# untitled.net
KiCad netlist of a schematic drawn in EAGLE
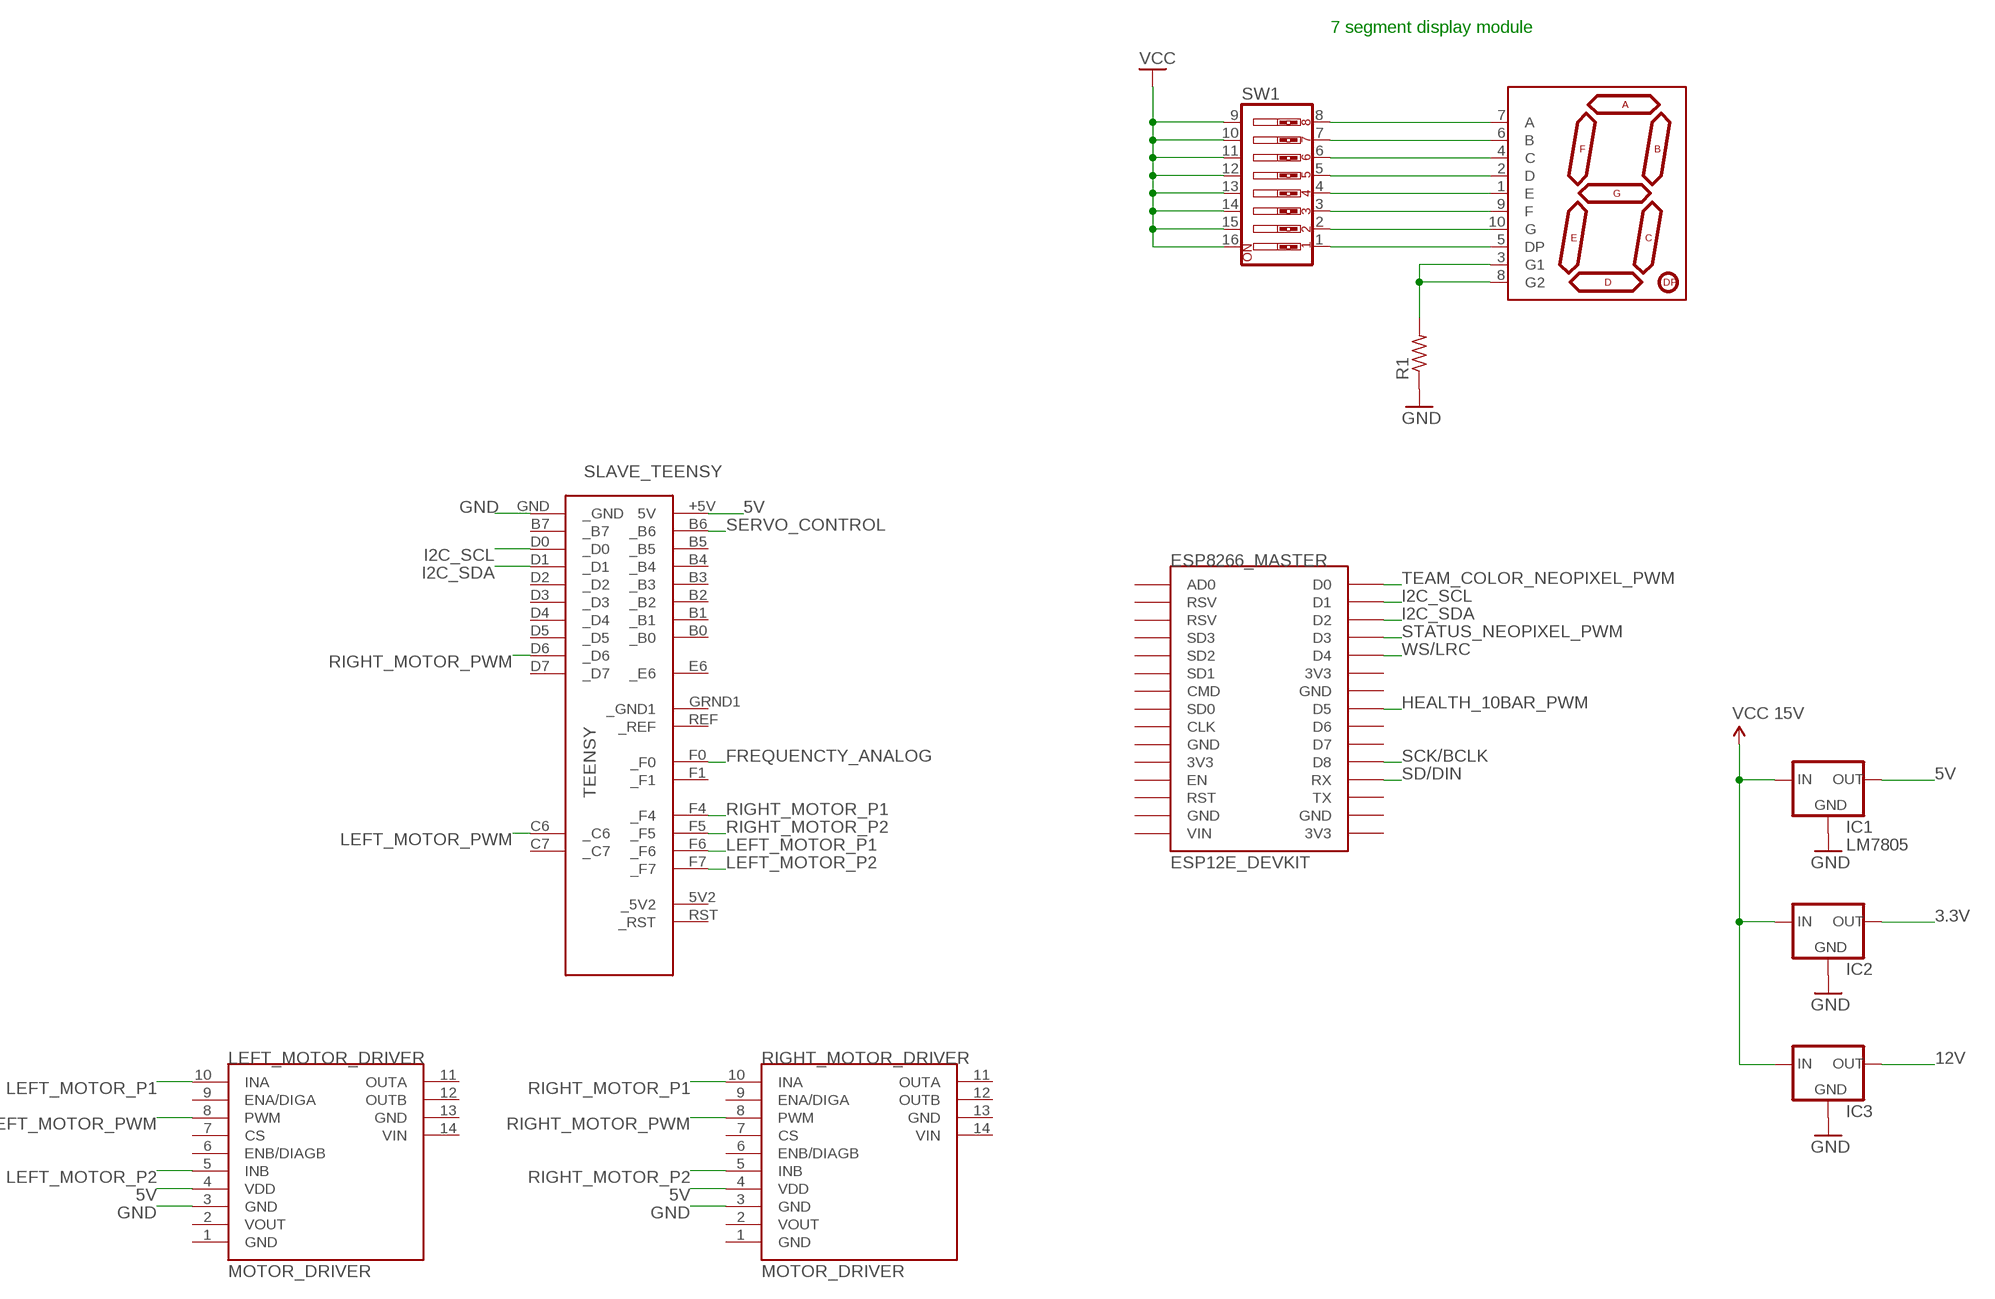
[diagram p0: schematic, sheet 1]

(export (version "E")
  (design (tool "Eeschema 10.0.6"))
  (components
    (comp (ref "ESP8266_MASTER")
      (value "ESP12E_DEVKIT")
      (footprint "eagle-import:ESP12E_DEVKIT")
      (libsource (lib "eagle-import") (part "ESP12E_DEVKIT"))
    )
    (comp (ref "IC1")
      (value "LM7805")
      (footprint "eagle-import:TO-220-ALT")
      (libsource (lib "eagle-import") (part "V_REG_78XX-TO-220"))
    )
    (comp (ref "IC2")
      (value "V_REG_78XX-TO-220")
      (footprint "eagle-import:TO-220-ALT")
      (libsource (lib "eagle-import") (part "V_REG_78XX-TO-220"))
    )
    (comp (ref "IC3")
      (value "V_REG_78XX-TO-220")
      (footprint "eagle-import:TO-220-ALT")
      (libsource (lib "eagle-import") (part "V_REG_78XX-TO-220"))
    )
    (comp (ref "LEFT_MOTOR_DRIVER")
      (value "MOTOR_DRIVER")
      (footprint "eagle-import:VNH5019A_MOTORDRIVER_CARIER_POLOLU")
      (libsource (lib "eagle-import") (part "MOTOR_DRIVER"))
    )
    (comp (ref "R1")
      (value "R-US_0204/2V")
      (footprint "eagle-import:0204V")
      (libsource (lib "eagle-import") (part "R-US_0204/2V"))
    )
    (comp (ref "RIGHT_MOTOR_DRIVER")
      (value "MOTOR_DRIVER")
      (footprint "eagle-import:VNH5019A_MOTORDRIVER_CARIER_POLOLU")
      (libsource (lib "eagle-import") (part "MOTOR_DRIVER"))
    )
    (comp (ref "SLAVE_TEENSY")
      (value "TEENSY")
      (footprint "eagle-import:TEENSY")
      (libsource (lib "eagle-import") (part "TEENSY"))
    )
    (comp (ref "SW1")
      (value "SW_DIP-8")
      (footprint "eagle-import:DIPSWITCH-08")
      (libsource (lib "eagle-import") (part "SW_DIP-8"))
    )
    (comp (ref "U$2")
      (value "7-SEGMENT-DISPLAYPTH")
      (footprint "eagle-import:7-SEGMENT-DISPLAY")
      (libsource (lib "eagle-import") (part "7-SEGMENT-DISPLAYPTH"))
    )
  )
  (nets
    (net (code "1") (name "/3.3V") (class "Default")
      (node (ref "IC2") (pin "OUT") (pinfunction "OUT_OUT") (pintype "output"))
    )
    (net (code "2") (name "/5V") (class "Default")
      (node (ref "IC1") (pin "OUT") (pinfunction "OUT_OUT") (pintype "output"))
      (node (ref "LEFT_MOTOR_DRIVER") (pin "4") (pinfunction "VDD_4") (pintype "bidirectional"))
      (node (ref "RIGHT_MOTOR_DRIVER") (pin "4") (pinfunction "VDD_4") (pintype "bidirectional"))
      (node (ref "SLAVE_TEENSY") (pin "+5V") (pinfunction "5V_+5V") (pintype "bidirectional"))
    )
    (net (code "3") (name "/12V") (class "Default")
      (node (ref "IC3") (pin "OUT") (pinfunction "OUT_OUT") (pintype "output"))
    )
    (net (code "4") (name "/FREQUENCTY_ANALOG") (class "Default")
      (node (ref "SLAVE_TEENSY") (pin "F0") (pinfunction "_F0_F0") (pintype "bidirectional"))
    )
    (net (code "5") (name "/HEALTH_10BAR_PWM") (class "Default")
      (node (ref "ESP8266_MASTER") (pin "D5") (pinfunction "D5_D5") (pintype "bidirectional"))
    )
    (net (code "6") (name "/I2C_SCL") (class "Default")
      (node (ref "ESP8266_MASTER") (pin "D1") (pinfunction "D1_D1") (pintype "bidirectional"))
      (node (ref "SLAVE_TEENSY") (pin "D0") (pinfunction "_D0_D0") (pintype "bidirectional"))
    )
    (net (code "7") (name "/I2C_SDA") (class "Default")
      (node (ref "ESP8266_MASTER") (pin "D2") (pinfunction "D2_D2") (pintype "bidirectional"))
      (node (ref "SLAVE_TEENSY") (pin "D1") (pinfunction "_D1_D1") (pintype "bidirectional"))
    )
    (net (code "8") (name "/LEFT_MOTOR_P1") (class "Default")
      (node (ref "LEFT_MOTOR_DRIVER") (pin "10") (pinfunction "INA_10") (pintype "bidirectional"))
      (node (ref "SLAVE_TEENSY") (pin "F6") (pinfunction "_F6_F6") (pintype "bidirectional"))
    )
    (net (code "9") (name "/LEFT_MOTOR_P2") (class "Default")
      (node (ref "LEFT_MOTOR_DRIVER") (pin "5") (pinfunction "INB_5") (pintype "bidirectional"))
      (node (ref "SLAVE_TEENSY") (pin "F7") (pinfunction "_F7_F7") (pintype "bidirectional"))
    )
    (net (code "10") (name "/LEFT_MOTOR_PWM") (class "Default")
      (node (ref "LEFT_MOTOR_DRIVER") (pin "8") (pinfunction "PWM_8") (pintype "bidirectional"))
      (node (ref "SLAVE_TEENSY") (pin "C6") (pinfunction "_C6_C6") (pintype "bidirectional"))
    )
    (net (code "11") (name "/RIGHT_MOTOR_P1") (class "Default")
      (node (ref "RIGHT_MOTOR_DRIVER") (pin "10") (pinfunction "INA_10") (pintype "bidirectional"))
      (node (ref "SLAVE_TEENSY") (pin "F4") (pinfunction "_F4_F4") (pintype "bidirectional"))
    )
    (net (code "12") (name "/RIGHT_MOTOR_P2") (class "Default")
      (node (ref "RIGHT_MOTOR_DRIVER") (pin "5") (pinfunction "INB_5") (pintype "bidirectional"))
      (node (ref "SLAVE_TEENSY") (pin "F5") (pinfunction "_F5_F5") (pintype "bidirectional"))
    )
    (net (code "13") (name "/RIGHT_MOTOR_PWM") (class "Default")
      (node (ref "RIGHT_MOTOR_DRIVER") (pin "8") (pinfunction "PWM_8") (pintype "bidirectional"))
      (node (ref "SLAVE_TEENSY") (pin "D6") (pinfunction "_D6_D6") (pintype "bidirectional"))
    )
    (net (code "14") (name "/SCK{slash}BCLK") (class "Default")
      (node (ref "ESP8266_MASTER") (pin "D8") (pinfunction "D8_D8") (pintype "bidirectional"))
    )
    (net (code "15") (name "/SD{slash}DIN") (class "Default")
      (node (ref "ESP8266_MASTER") (pin "RX") (pinfunction "RX_RX") (pintype "bidirectional"))
    )
    (net (code "16") (name "/SERVO_CONTROL") (class "Default")
      (node (ref "SLAVE_TEENSY") (pin "B6") (pinfunction "_B6_B6") (pintype "bidirectional"))
    )
    (net (code "17") (name "/STATUS_NEOPIXEL_PWM") (class "Default")
      (node (ref "ESP8266_MASTER") (pin "D3") (pinfunction "D3_D3") (pintype "bidirectional"))
    )
    (net (code "18") (name "/TEAM_COLOR_NEOPIXEL_PWM") (class "Default")
      (node (ref "ESP8266_MASTER") (pin "D0") (pinfunction "D0_D0") (pintype "bidirectional"))
    )
    (net (code "19") (name "/WS{slash}LRC") (class "Default")
      (node (ref "ESP8266_MASTER") (pin "D4") (pinfunction "D4_D4") (pintype "bidirectional"))
    )
    (net (code "20") (name "GND") (class "Default")
      (node (ref "IC1") (pin "GND") (pinfunction "GND_GND") (pintype "input"))
      (node (ref "IC2") (pin "GND") (pinfunction "GND_GND") (pintype "input"))
      (node (ref "IC3") (pin "GND") (pinfunction "GND_GND") (pintype "input"))
      (node (ref "LEFT_MOTOR_DRIVER") (pin "3") (pinfunction "GND_3") (pintype "bidirectional"))
      (node (ref "R1") (pin "1") (pinfunction "1_1") (pintype "passive"))
      (node (ref "RIGHT_MOTOR_DRIVER") (pin "3") (pinfunction "GND_3") (pintype "bidirectional"))
      (node (ref "SLAVE_TEENSY") (pin "GND") (pinfunction "_GND_GND") (pintype "bidirectional"))
    )
    (net (code "21") (name "Net-(U$2-A)") (class "Default")
      (node (ref "SW1") (pin "8") (pinfunction "8_8") (pintype "passive"))
      (node (ref "U$2") (pin "7") (pinfunction "A_7") (pintype "bidirectional"))
    )
    (net (code "22") (name "Net-(U$2-B)") (class "Default")
      (node (ref "SW1") (pin "7") (pinfunction "7_7") (pintype "passive"))
      (node (ref "U$2") (pin "6") (pinfunction "B_6") (pintype "bidirectional"))
    )
    (net (code "23") (name "Net-(U$2-C)") (class "Default")
      (node (ref "SW1") (pin "6") (pinfunction "6_6") (pintype "passive"))
      (node (ref "U$2") (pin "4") (pinfunction "C_4") (pintype "bidirectional"))
    )
    (net (code "24") (name "Net-(U$2-D)") (class "Default")
      (node (ref "SW1") (pin "5") (pinfunction "5_5") (pintype "passive"))
      (node (ref "U$2") (pin "2") (pinfunction "D_2") (pintype "bidirectional"))
    )
    (net (code "25") (name "Net-(U$2-DP)") (class "Default")
      (node (ref "SW1") (pin "1") (pinfunction "1_1") (pintype "passive"))
      (node (ref "U$2") (pin "5") (pinfunction "DP_5") (pintype "bidirectional"))
    )
    (net (code "26") (name "Net-(U$2-E)") (class "Default")
      (node (ref "SW1") (pin "4") (pinfunction "4_4") (pintype "passive"))
      (node (ref "U$2") (pin "1") (pinfunction "E_1") (pintype "bidirectional"))
    )
    (net (code "27") (name "Net-(U$2-F)") (class "Default")
      (node (ref "SW1") (pin "3") (pinfunction "3_3") (pintype "passive"))
      (node (ref "U$2") (pin "9") (pinfunction "F_9") (pintype "bidirectional"))
    )
    (net (code "28") (name "Net-(U$2-G)") (class "Default")
      (node (ref "SW1") (pin "2") (pinfunction "2_2") (pintype "passive"))
      (node (ref "U$2") (pin "10") (pinfunction "G_10") (pintype "bidirectional"))
    )
    (net (code "29") (name "Net-(U$2-G1)") (class "Default")
      (node (ref "R1") (pin "2") (pinfunction "2_2") (pintype "passive"))
      (node (ref "U$2") (pin "3") (pinfunction "G1_3") (pintype "bidirectional"))
      (node (ref "U$2") (pin "8") (pinfunction "G2_8") (pintype "bidirectional"))
    )
    (net (code "30") (name "VCC") (class "Default")
      (node (ref "IC1") (pin "IN") (pinfunction "IN_IN") (pintype "input"))
      (node (ref "IC2") (pin "IN") (pinfunction "IN_IN") (pintype "input"))
      (node (ref "IC3") (pin "IN") (pinfunction "IN_IN") (pintype "input"))
      (node (ref "SW1") (pin "10") (pinfunction "10_10") (pintype "passive"))
      (node (ref "SW1") (pin "11") (pinfunction "11_11") (pintype "passive"))
      (node (ref "SW1") (pin "12") (pinfunction "12_12") (pintype "passive"))
      (node (ref "SW1") (pin "13") (pinfunction "13_13") (pintype "passive"))
      (node (ref "SW1") (pin "14") (pinfunction "14_14") (pintype "passive"))
      (node (ref "SW1") (pin "15") (pinfunction "15_15") (pintype "passive"))
      (node (ref "SW1") (pin "16") (pinfunction "16_16") (pintype "passive"))
      (node (ref "SW1") (pin "9") (pinfunction "9_9") (pintype "passive"))
    )
    (net (code "31") (name "unconnected-(ESP8266_MASTER-3V3-Pad3V3@0)") (class "Default")
      (node (ref "ESP8266_MASTER") (pin "3V3@0") (pinfunction "3V3_3V3@0") (pintype "bidirectional"))
    )
    (net (code "32") (name "unconnected-(ESP8266_MASTER-3V3-Pad3V3@1)") (class "Default")
      (node (ref "ESP8266_MASTER") (pin "3V3@1") (pinfunction "3V3_3V3@1") (pintype "bidirectional"))
    )
    (net (code "33") (name "unconnected-(ESP8266_MASTER-3V3-Pad3V3@2)") (class "Default")
      (node (ref "ESP8266_MASTER") (pin "3V3@2") (pinfunction "3V3_3V3@2") (pintype "bidirectional"))
    )
    (net (code "34") (name "unconnected-(ESP8266_MASTER-GND-PadGND@0)") (class "Default")
      (node (ref "ESP8266_MASTER") (pin "GND@0") (pinfunction "GND_GND@0") (pintype "bidirectional"))
    )
    (net (code "35") (name "unconnected-(ESP8266_MASTER-GND-PadGND@1)") (class "Default")
      (node (ref "ESP8266_MASTER") (pin "GND@1") (pinfunction "GND_GND@1") (pintype "bidirectional"))
    )
    (net (code "36") (name "unconnected-(ESP8266_MASTER-GND-PadGND@2)") (class "Default")
      (node (ref "ESP8266_MASTER") (pin "GND@2") (pinfunction "GND_GND@2") (pintype "bidirectional"))
    )
    (net (code "37") (name "unconnected-(ESP8266_MASTER-GND-PadGND@3)") (class "Default")
      (node (ref "ESP8266_MASTER") (pin "GND@3") (pinfunction "GND_GND@3") (pintype "bidirectional"))
    )
    (net (code "38") (name "unconnected-(ESP8266_MASTER-PadAD0)") (class "Default")
      (node (ref "ESP8266_MASTER") (pin "AD0") (pinfunction "AD0_AD0") (pintype "bidirectional"))
    )
    (net (code "39") (name "unconnected-(ESP8266_MASTER-PadCLK)") (class "Default")
      (node (ref "ESP8266_MASTER") (pin "CLK") (pinfunction "CLK_CLK") (pintype "bidirectional"))
    )
    (net (code "40") (name "unconnected-(ESP8266_MASTER-PadCMD)") (class "Default")
      (node (ref "ESP8266_MASTER") (pin "CMD") (pinfunction "CMD_CMD") (pintype "bidirectional"))
    )
    (net (code "41") (name "unconnected-(ESP8266_MASTER-PadD6)") (class "Default")
      (node (ref "ESP8266_MASTER") (pin "D6") (pinfunction "D6_D6") (pintype "bidirectional"))
    )
    (net (code "42") (name "unconnected-(ESP8266_MASTER-PadD7)") (class "Default")
      (node (ref "ESP8266_MASTER") (pin "D7") (pinfunction "D7_D7") (pintype "bidirectional"))
    )
    (net (code "43") (name "unconnected-(ESP8266_MASTER-PadEN)") (class "Default")
      (node (ref "ESP8266_MASTER") (pin "EN") (pinfunction "EN_EN") (pintype "bidirectional"))
    )
    (net (code "44") (name "unconnected-(ESP8266_MASTER-PadRST)") (class "Default")
      (node (ref "ESP8266_MASTER") (pin "RST") (pinfunction "RST_RST") (pintype "bidirectional"))
    )
    (net (code "45") (name "unconnected-(ESP8266_MASTER-PadSD0)") (class "Default")
      (node (ref "ESP8266_MASTER") (pin "SD0") (pinfunction "SD0_SD0") (pintype "bidirectional"))
    )
    (net (code "46") (name "unconnected-(ESP8266_MASTER-PadSD1)") (class "Default")
      (node (ref "ESP8266_MASTER") (pin "SD1") (pinfunction "SD1_SD1") (pintype "bidirectional"))
    )
    (net (code "47") (name "unconnected-(ESP8266_MASTER-PadSD2)") (class "Default")
      (node (ref "ESP8266_MASTER") (pin "SD2") (pinfunction "SD2_SD2") (pintype "bidirectional"))
    )
    (net (code "48") (name "unconnected-(ESP8266_MASTER-PadSD3)") (class "Default")
      (node (ref "ESP8266_MASTER") (pin "SD3") (pinfunction "SD3_SD3") (pintype "bidirectional"))
    )
    (net (code "49") (name "unconnected-(ESP8266_MASTER-PadTX)") (class "Default")
      (node (ref "ESP8266_MASTER") (pin "TX") (pinfunction "TX_TX") (pintype "bidirectional"))
    )
    (net (code "50") (name "unconnected-(ESP8266_MASTER-PadVIN)") (class "Default")
      (node (ref "ESP8266_MASTER") (pin "VIN") (pinfunction "VIN_VIN") (pintype "bidirectional"))
    )
    (net (code "51") (name "unconnected-(ESP8266_MASTER-RSV-PadRSV@0)") (class "Default")
      (node (ref "ESP8266_MASTER") (pin "RSV@0") (pinfunction "RSV_RSV@0") (pintype "bidirectional"))
    )
    (net (code "52") (name "unconnected-(ESP8266_MASTER-RSV-PadRSV@1)") (class "Default")
      (node (ref "ESP8266_MASTER") (pin "RSV@1") (pinfunction "RSV_RSV@1") (pintype "bidirectional"))
    )
    (net (code "53") (name "unconnected-(LEFT_MOTOR_DRIVER-CS-Pad7)") (class "Default")
      (node (ref "LEFT_MOTOR_DRIVER") (pin "7") (pinfunction "CS_7") (pintype "bidirectional"))
    )
    (net (code "54") (name "unconnected-(LEFT_MOTOR_DRIVER-ENA{slash}DIGA-Pad9)") (class "Default")
      (node (ref "LEFT_MOTOR_DRIVER") (pin "9") (pinfunction "ENA/DIGA_9") (pintype "bidirectional"))
    )
    (net (code "55") (name "unconnected-(LEFT_MOTOR_DRIVER-ENB{slash}DIAGB-Pad6)") (class "Default")
      (node (ref "LEFT_MOTOR_DRIVER") (pin "6") (pinfunction "ENB/DIAGB_6") (pintype "bidirectional"))
    )
    (net (code "56") (name "unconnected-(LEFT_MOTOR_DRIVER-GND-Pad1)") (class "Default")
      (node (ref "LEFT_MOTOR_DRIVER") (pin "1") (pinfunction "GND_1") (pintype "bidirectional"))
    )
    (net (code "57") (name "unconnected-(LEFT_MOTOR_DRIVER-GND-Pad13)") (class "Default")
      (node (ref "LEFT_MOTOR_DRIVER") (pin "13") (pinfunction "GND_13") (pintype "bidirectional"))
    )
    (net (code "58") (name "unconnected-(LEFT_MOTOR_DRIVER-OUTA-Pad11)") (class "Default")
      (node (ref "LEFT_MOTOR_DRIVER") (pin "11") (pinfunction "OUTA_11") (pintype "bidirectional"))
    )
    (net (code "59") (name "unconnected-(LEFT_MOTOR_DRIVER-OUTB-Pad12)") (class "Default")
      (node (ref "LEFT_MOTOR_DRIVER") (pin "12") (pinfunction "OUTB_12") (pintype "bidirectional"))
    )
    (net (code "60") (name "unconnected-(LEFT_MOTOR_DRIVER-VIN-Pad14)") (class "Default")
      (node (ref "LEFT_MOTOR_DRIVER") (pin "14") (pinfunction "VIN_14") (pintype "bidirectional"))
    )
    (net (code "61") (name "unconnected-(LEFT_MOTOR_DRIVER-VOUT-Pad2)") (class "Default")
      (node (ref "LEFT_MOTOR_DRIVER") (pin "2") (pinfunction "VOUT_2") (pintype "bidirectional"))
    )
    (net (code "62") (name "unconnected-(RIGHT_MOTOR_DRIVER-CS-Pad7)") (class "Default")
      (node (ref "RIGHT_MOTOR_DRIVER") (pin "7") (pinfunction "CS_7") (pintype "bidirectional"))
    )
    (net (code "63") (name "unconnected-(RIGHT_MOTOR_DRIVER-ENA{slash}DIGA-Pad9)") (class "Default")
      (node (ref "RIGHT_MOTOR_DRIVER") (pin "9") (pinfunction "ENA/DIGA_9") (pintype "bidirectional"))
    )
    (net (code "64") (name "unconnected-(RIGHT_MOTOR_DRIVER-ENB{slash}DIAGB-Pad6)") (class "Default")
      (node (ref "RIGHT_MOTOR_DRIVER") (pin "6") (pinfunction "ENB/DIAGB_6") (pintype "bidirectional"))
    )
    (net (code "65") (name "unconnected-(RIGHT_MOTOR_DRIVER-GND-Pad1)") (class "Default")
      (node (ref "RIGHT_MOTOR_DRIVER") (pin "1") (pinfunction "GND_1") (pintype "bidirectional"))
    )
    (net (code "66") (name "unconnected-(RIGHT_MOTOR_DRIVER-GND-Pad13)") (class "Default")
      (node (ref "RIGHT_MOTOR_DRIVER") (pin "13") (pinfunction "GND_13") (pintype "bidirectional"))
    )
    (net (code "67") (name "unconnected-(RIGHT_MOTOR_DRIVER-OUTA-Pad11)") (class "Default")
      (node (ref "RIGHT_MOTOR_DRIVER") (pin "11") (pinfunction "OUTA_11") (pintype "bidirectional"))
    )
    (net (code "68") (name "unconnected-(RIGHT_MOTOR_DRIVER-OUTB-Pad12)") (class "Default")
      (node (ref "RIGHT_MOTOR_DRIVER") (pin "12") (pinfunction "OUTB_12") (pintype "bidirectional"))
    )
    (net (code "69") (name "unconnected-(RIGHT_MOTOR_DRIVER-VIN-Pad14)") (class "Default")
      (node (ref "RIGHT_MOTOR_DRIVER") (pin "14") (pinfunction "VIN_14") (pintype "bidirectional"))
    )
    (net (code "70") (name "unconnected-(RIGHT_MOTOR_DRIVER-VOUT-Pad2)") (class "Default")
      (node (ref "RIGHT_MOTOR_DRIVER") (pin "2") (pinfunction "VOUT_2") (pintype "bidirectional"))
    )
    (net (code "71") (name "unconnected-(SLAVE_TEENSY-_5V2-Pad5V2)") (class "Default")
      (node (ref "SLAVE_TEENSY") (pin "5V2") (pinfunction "_5V2_5V2") (pintype "bidirectional"))
    )
    (net (code "72") (name "unconnected-(SLAVE_TEENSY-_B0-PadB0)") (class "Default")
      (node (ref "SLAVE_TEENSY") (pin "B0") (pinfunction "_B0_B0") (pintype "bidirectional"))
    )
    (net (code "73") (name "unconnected-(SLAVE_TEENSY-_B1-PadB1)") (class "Default")
      (node (ref "SLAVE_TEENSY") (pin "B1") (pinfunction "_B1_B1") (pintype "bidirectional"))
    )
    (net (code "74") (name "unconnected-(SLAVE_TEENSY-_B2-PadB2)") (class "Default")
      (node (ref "SLAVE_TEENSY") (pin "B2") (pinfunction "_B2_B2") (pintype "bidirectional"))
    )
    (net (code "75") (name "unconnected-(SLAVE_TEENSY-_B3-PadB3)") (class "Default")
      (node (ref "SLAVE_TEENSY") (pin "B3") (pinfunction "_B3_B3") (pintype "bidirectional"))
    )
    (net (code "76") (name "unconnected-(SLAVE_TEENSY-_B4-PadB4)") (class "Default")
      (node (ref "SLAVE_TEENSY") (pin "B4") (pinfunction "_B4_B4") (pintype "bidirectional"))
    )
    (net (code "77") (name "unconnected-(SLAVE_TEENSY-_B5-PadB5)") (class "Default")
      (node (ref "SLAVE_TEENSY") (pin "B5") (pinfunction "_B5_B5") (pintype "bidirectional"))
    )
    (net (code "78") (name "unconnected-(SLAVE_TEENSY-_B7-PadB7)") (class "Default")
      (node (ref "SLAVE_TEENSY") (pin "B7") (pinfunction "_B7_B7") (pintype "bidirectional"))
    )
    (net (code "79") (name "unconnected-(SLAVE_TEENSY-_C7-PadC7)") (class "Default")
      (node (ref "SLAVE_TEENSY") (pin "C7") (pinfunction "_C7_C7") (pintype "bidirectional"))
    )
    (net (code "80") (name "unconnected-(SLAVE_TEENSY-_D2-PadD2)") (class "Default")
      (node (ref "SLAVE_TEENSY") (pin "D2") (pinfunction "_D2_D2") (pintype "bidirectional"))
    )
    (net (code "81") (name "unconnected-(SLAVE_TEENSY-_D3-PadD3)") (class "Default")
      (node (ref "SLAVE_TEENSY") (pin "D3") (pinfunction "_D3_D3") (pintype "bidirectional"))
    )
    (net (code "82") (name "unconnected-(SLAVE_TEENSY-_D4-PadD4)") (class "Default")
      (node (ref "SLAVE_TEENSY") (pin "D4") (pinfunction "_D4_D4") (pintype "bidirectional"))
    )
    (net (code "83") (name "unconnected-(SLAVE_TEENSY-_D5-PadD5)") (class "Default")
      (node (ref "SLAVE_TEENSY") (pin "D5") (pinfunction "_D5_D5") (pintype "bidirectional"))
    )
    (net (code "84") (name "unconnected-(SLAVE_TEENSY-_D7-PadD7)") (class "Default")
      (node (ref "SLAVE_TEENSY") (pin "D7") (pinfunction "_D7_D7") (pintype "bidirectional"))
    )
    (net (code "85") (name "unconnected-(SLAVE_TEENSY-_E6-PadE6)") (class "Default")
      (node (ref "SLAVE_TEENSY") (pin "E6") (pinfunction "_E6_E6") (pintype "bidirectional"))
    )
    (net (code "86") (name "unconnected-(SLAVE_TEENSY-_F1-PadF1)") (class "Default")
      (node (ref "SLAVE_TEENSY") (pin "F1") (pinfunction "_F1_F1") (pintype "bidirectional"))
    )
    (net (code "87") (name "unconnected-(SLAVE_TEENSY-_GND1-PadGRND1)") (class "Default")
      (node (ref "SLAVE_TEENSY") (pin "GRND1") (pinfunction "_GND1_GRND1") (pintype "bidirectional"))
    )
    (net (code "88") (name "unconnected-(SLAVE_TEENSY-_REF-PadREF)") (class "Default")
      (node (ref "SLAVE_TEENSY") (pin "REF") (pinfunction "_REF_REF") (pintype "bidirectional"))
    )
    (net (code "89") (name "unconnected-(SLAVE_TEENSY-_RST-PadRST)") (class "Default")
      (node (ref "SLAVE_TEENSY") (pin "RST") (pinfunction "_RST_RST") (pintype "bidirectional"))
    )
  )
)
